# NBMC_SCHEMATIC_with_LBM313.net
KiCad netlist of a schematic drawn in EAGLE
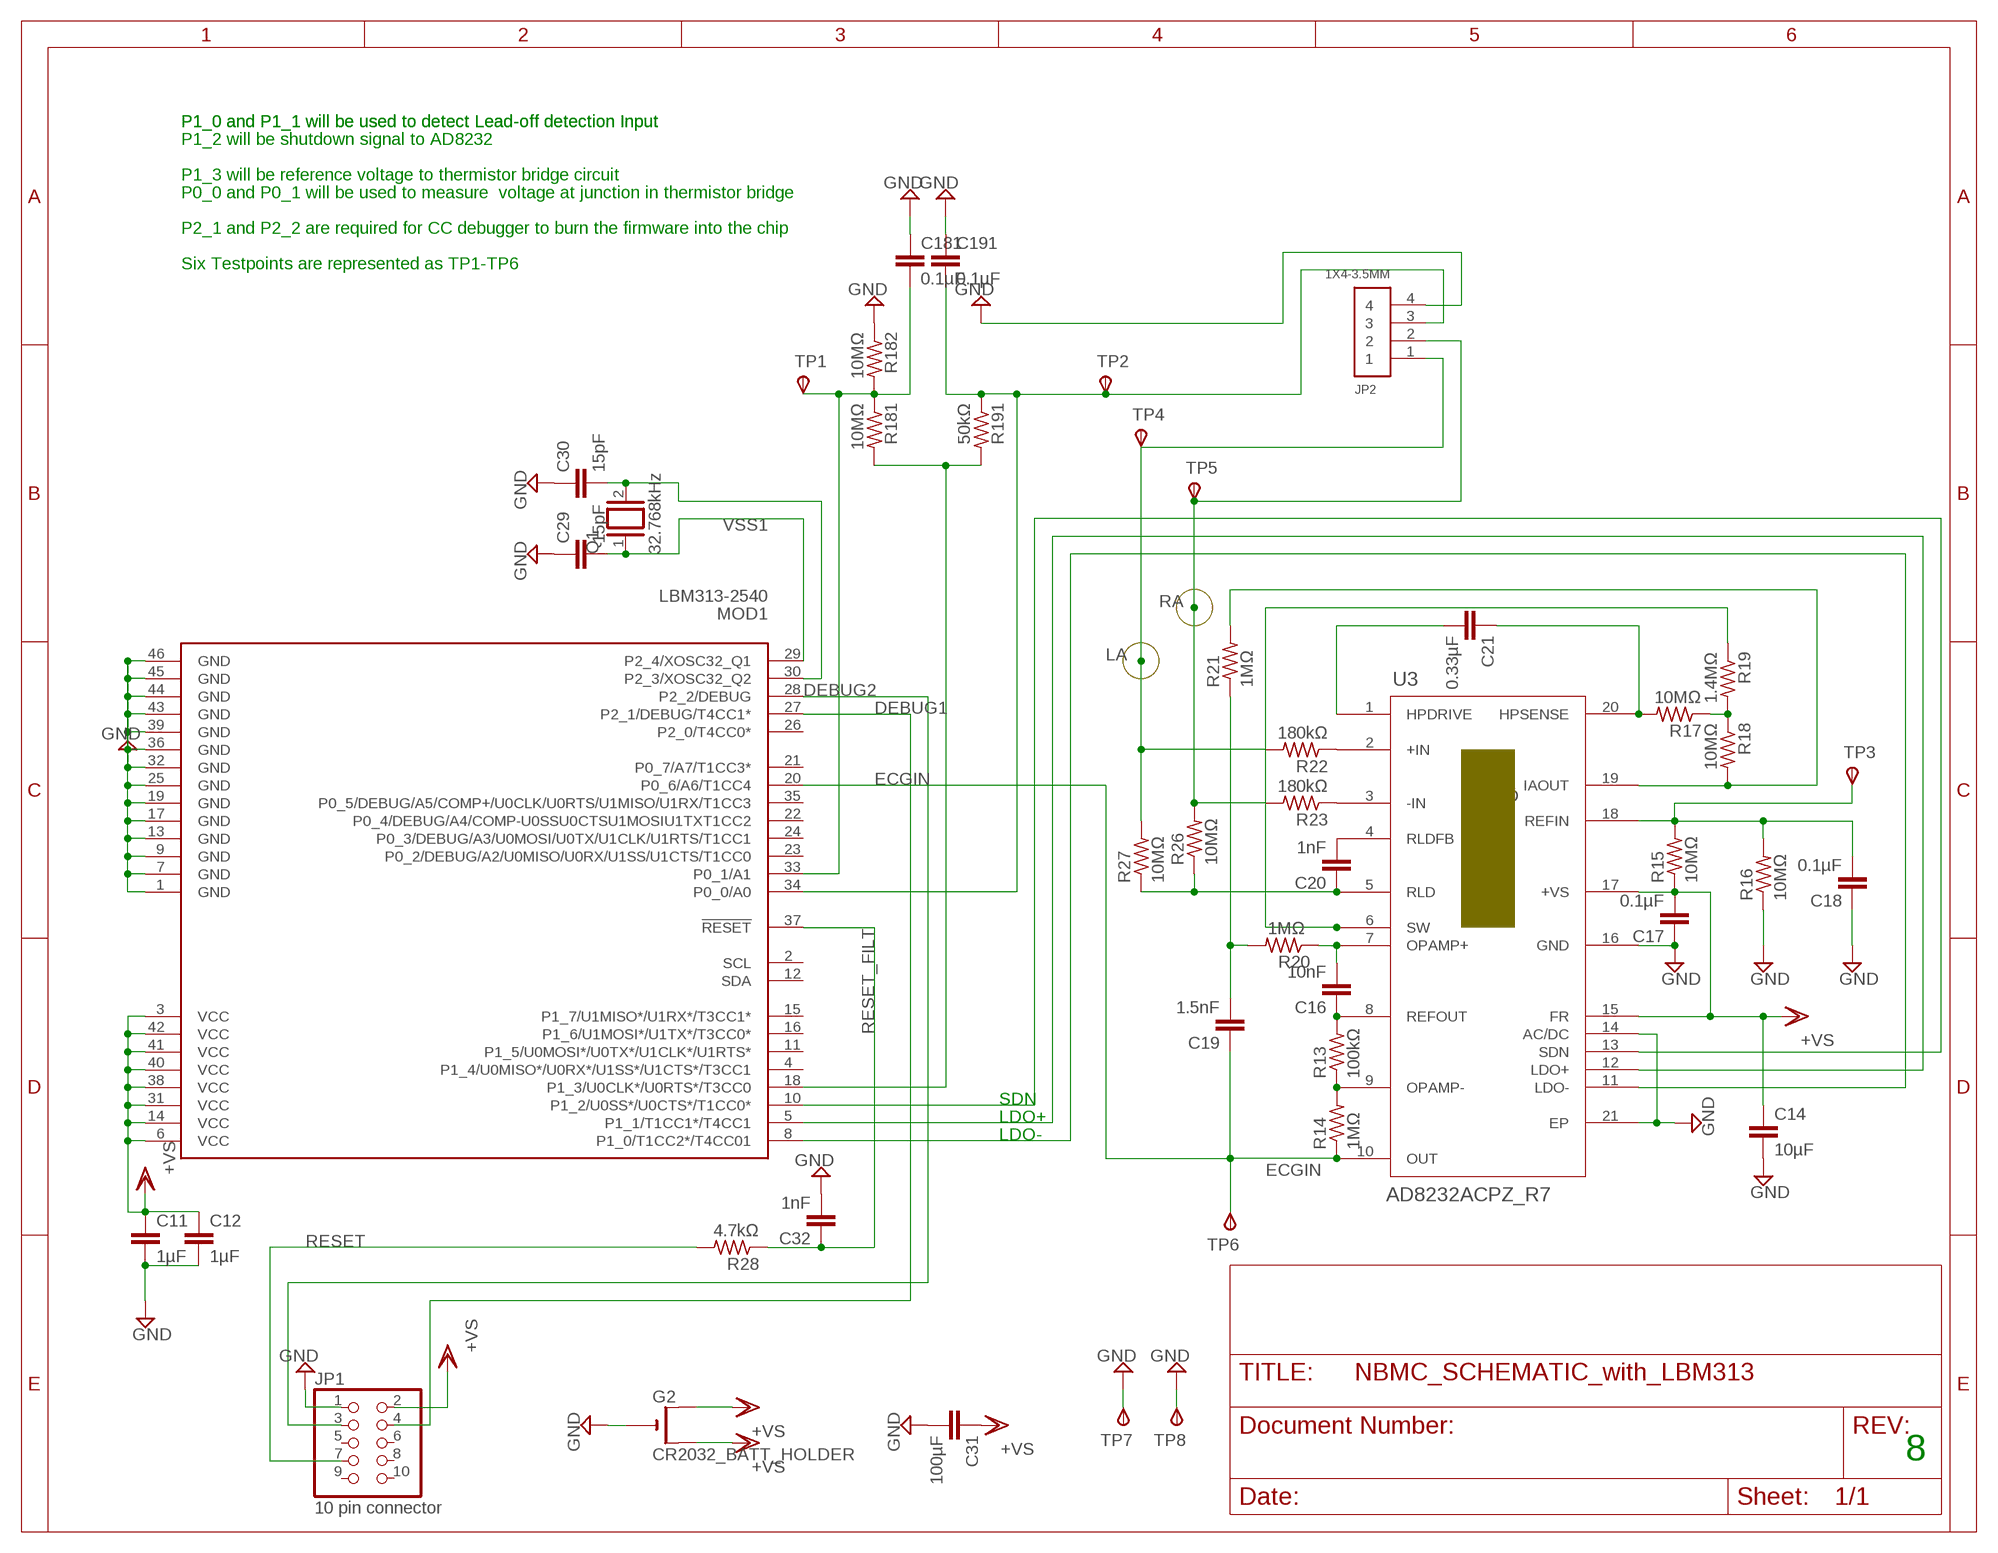
[diagram p0: schematic, sheet 1]

(export (version "E")
  (design (tool "Eeschema 10.0.6"))
  (components
    (comp (ref "C11")
      (value "1µF")
      (footprint "eagle-import:C0402")
      (libsource (lib "eagle-import") (part "C-EUC0402"))
    )
    (comp (ref "C12")
      (value "1µF")
      (footprint "eagle-import:C0402")
      (libsource (lib "eagle-import") (part "C-EUC0402"))
    )
    (comp (ref "C14")
      (value "10µF")
      (footprint "eagle-import:C0402")
      (libsource (lib "eagle-import") (part "C-EUC0402"))
    )
    (comp (ref "C16")
      (value "10nF")
      (footprint "eagle-import:C0402")
      (libsource (lib "eagle-import") (part "C-EUC0402"))
    )
    (comp (ref "C17")
      (value "0.1µF")
      (footprint "eagle-import:C0402")
      (libsource (lib "eagle-import") (part "C-EUC0402"))
    )
    (comp (ref "C18")
      (value "0.1µF")
      (footprint "eagle-import:C0402")
      (libsource (lib "eagle-import") (part "C-EUC0402"))
    )
    (comp (ref "C19")
      (value "1.5nF")
      (footprint "eagle-import:C0402")
      (libsource (lib "eagle-import") (part "C-EUC0402"))
    )
    (comp (ref "C20")
      (value "1nF")
      (footprint "eagle-import:C0402")
      (libsource (lib "eagle-import") (part "C-EUC0402"))
    )
    (comp (ref "C21")
      (value "0.33µF")
      (footprint "eagle-import:C0402")
      (libsource (lib "eagle-import") (part "C-EUC0402"))
    )
    (comp (ref "C29")
      (value "15pF")
      (footprint "eagle-import:C0402")
      (libsource (lib "eagle-import") (part "C-EUC0402"))
    )
    (comp (ref "C30")
      (value "15pF")
      (footprint "eagle-import:C0402")
      (libsource (lib "eagle-import") (part "C-EUC0402"))
    )
    (comp (ref "C31")
      (value "100µF")
      (footprint "eagle-import:C1210")
      (libsource (lib "eagle-import") (part "resistor_C-EUC1210"))
    )
    (comp (ref "C32")
      (value "1nF")
      (footprint "eagle-import:C0402")
      (libsource (lib "eagle-import") (part "C-EUC0402"))
    )
    (comp (ref "C181")
      (value "0.1µF")
      (footprint "eagle-import:C0402")
      (libsource (lib "eagle-import") (part "C-EUC0402"))
    )
    (comp (ref "C191")
      (value "0.1µF")
      (footprint "eagle-import:C0402")
      (libsource (lib "eagle-import") (part "C-EUC0402"))
    )
    (comp (ref "G2")
      (value "CR2032_BATT_HOLDER")
      (footprint "eagle-import:CR2032-SMD")
      (libsource (lib "eagle-import") (part "CR2032SMT"))
    )
    (comp (ref "JP1")
      (value "10 pin connector")
      (footprint "eagle-import:2X05")
      (libsource (lib "eagle-import") (part "PINHD-2X5"))
    )
    (comp (ref "JP2")
      (value "1X4-3.5MM")
      (footprint "eagle-import:1X04-3.5MM")
      (libsource (lib "eagle-import") (part "1X4-3.5MM"))
    )
    (comp (ref "MOD1")
      (value "LBM313-2540")
      (footprint "eagle-import:LBM313-2540")
      (libsource (lib "eagle-import") (part "LBM313-2540"))
    )
    (comp (ref "Q1")
      (value "32.768kHz")
      (footprint "eagle-import:Q")
      (libsource (lib "eagle-import") (part "XTAL"))
    )
    (comp (ref "R13")
      (value "100kΩ")
      (footprint "eagle-import:R0402")
      (libsource (lib "eagle-import") (part "R-US_R0402"))
    )
    (comp (ref "R14")
      (value "1MΩ")
      (footprint "eagle-import:R0402")
      (libsource (lib "eagle-import") (part "R-US_R0402"))
    )
    (comp (ref "R15")
      (value "10MΩ")
      (footprint "eagle-import:R0402")
      (libsource (lib "eagle-import") (part "R-US_R0402"))
    )
    (comp (ref "R16")
      (value "10MΩ")
      (footprint "eagle-import:R0402")
      (libsource (lib "eagle-import") (part "R-US_R0402"))
    )
    (comp (ref "R17")
      (value "10MΩ")
      (footprint "eagle-import:R0402")
      (libsource (lib "eagle-import") (part "R-US_R0402"))
    )
    (comp (ref "R18")
      (value "10MΩ")
      (footprint "eagle-import:R0402")
      (libsource (lib "eagle-import") (part "R-US_R0402"))
    )
    (comp (ref "R19")
      (value "1.4MΩ")
      (footprint "eagle-import:R0402")
      (libsource (lib "eagle-import") (part "R-US_R0402"))
    )
    (comp (ref "R20")
      (value "1MΩ")
      (footprint "eagle-import:R0402")
      (libsource (lib "eagle-import") (part "R-US_R0402"))
    )
    (comp (ref "R21")
      (value "1MΩ")
      (footprint "eagle-import:R0402")
      (libsource (lib "eagle-import") (part "R-US_R0402"))
    )
    (comp (ref "R22")
      (value "180kΩ")
      (footprint "eagle-import:R0402")
      (libsource (lib "eagle-import") (part "R-US_R0402"))
    )
    (comp (ref "R23")
      (value "180kΩ")
      (footprint "eagle-import:R0402")
      (libsource (lib "eagle-import") (part "R-US_R0402"))
    )
    (comp (ref "R26")
      (value "10MΩ")
      (footprint "eagle-import:R0402")
      (libsource (lib "eagle-import") (part "R-US_R0402"))
    )
    (comp (ref "R27")
      (value "10MΩ")
      (footprint "eagle-import:R0402")
      (libsource (lib "eagle-import") (part "R-US_R0402"))
    )
    (comp (ref "R28")
      (value "4.7kΩ")
      (footprint "eagle-import:R0402")
      (libsource (lib "eagle-import") (part "R-US_R0402"))
    )
    (comp (ref "R181")
      (value "10MΩ")
      (footprint "eagle-import:R0402")
      (libsource (lib "eagle-import") (part "R-US_R0402"))
    )
    (comp (ref "R182")
      (value "10MΩ")
      (footprint "eagle-import:R0402")
      (libsource (lib "eagle-import") (part "R-US_R0402"))
    )
    (comp (ref "R191")
      (value "50kΩ")
      (footprint "eagle-import:R0402")
      (libsource (lib "eagle-import") (part "R-US_R0402"))
    )
    (comp (ref "TP1")
      (value "TPSTP09R")
      (footprint "eagle-import:TP09R")
      (libsource (lib "eagle-import") (part "TPSTP09R"))
    )
    (comp (ref "TP2")
      (value "TPSTP09R")
      (footprint "eagle-import:TP09R")
      (libsource (lib "eagle-import") (part "TPSTP09R"))
    )
    (comp (ref "TP3")
      (value "TPSTP09R")
      (footprint "eagle-import:TP09R")
      (libsource (lib "eagle-import") (part "TPSTP09R"))
    )
    (comp (ref "TP4")
      (value "TPSTP09R")
      (footprint "eagle-import:TP09R")
      (libsource (lib "eagle-import") (part "TPSTP09R"))
    )
    (comp (ref "TP5")
      (value "TPSTP09R")
      (footprint "eagle-import:TP09R")
      (libsource (lib "eagle-import") (part "TPSTP09R"))
    )
    (comp (ref "TP6")
      (value "TPSTP09R")
      (footprint "eagle-import:TP09R")
      (libsource (lib "eagle-import") (part "TPSTP09R"))
    )
    (comp (ref "TP7")
      (value "TPSTP09R")
      (footprint "eagle-import:TP09R")
      (libsource (lib "eagle-import") (part "TPSTP09R"))
    )
    (comp (ref "TP8")
      (value "TPSTP09R")
      (footprint "eagle-import:TP09R")
      (libsource (lib "eagle-import") (part "TPSTP09R"))
    )
    (comp (ref "U3")
      (value "AD8232ACPZ_R7")
      (footprint "eagle-import:CP_20_10")
      (libsource (lib "eagle-import") (part "AD8232ACPZ_R7"))
    )
  )
  (nets
    (net (code "1") (name "+VS") (class "Default")
      (node (ref "C11") (pin "1") (pinfunction "1_1") (pintype "passive"))
      (node (ref "C12") (pin "1") (pinfunction "1_1") (pintype "passive"))
      (node (ref "C14") (pin "1") (pinfunction "1_1") (pintype "passive"))
      (node (ref "C17") (pin "2") (pinfunction "2_2") (pintype "passive"))
      (node (ref "C31") (pin "1") (pinfunction "1_1") (pintype "passive"))
      (node (ref "G2") (pin "1") (pinfunction "VS1_1") (pintype "passive"))
      (node (ref "G2") (pin "3") (pinfunction "VS2_3") (pintype "passive"))
      (node (ref "JP1") (pin "2") (pinfunction "2_2") (pintype "passive"))
      (node (ref "MOD1") (pin "14") (pinfunction "VCC_14") (pintype "bidirectional"))
      (node (ref "MOD1") (pin "3") (pinfunction "VCC_3") (pintype "bidirectional"))
      (node (ref "MOD1") (pin "31") (pinfunction "VCC_31") (pintype "bidirectional"))
      (node (ref "MOD1") (pin "38") (pinfunction "VCC_38") (pintype "bidirectional"))
      (node (ref "MOD1") (pin "40") (pinfunction "VCC_40") (pintype "bidirectional"))
      (node (ref "MOD1") (pin "41") (pinfunction "VCC_41") (pintype "bidirectional"))
      (node (ref "MOD1") (pin "42") (pinfunction "VCC_42") (pintype "bidirectional"))
      (node (ref "MOD1") (pin "6") (pinfunction "VCC_6") (pintype "bidirectional"))
      (node (ref "R15") (pin "1") (pinfunction "1_1") (pintype "passive"))
      (node (ref "U3") (pin "15") (pinfunction "FR_15") (pintype "passive"))
      (node (ref "U3") (pin "17") (pinfunction "+VS_17") (pintype "passive"))
    )
    (net (code "2") (name "/DEBUG1") (class "Default")
      (node (ref "JP1") (pin "4") (pinfunction "4_4") (pintype "passive"))
      (node (ref "MOD1") (pin "27") (pinfunction "P2_1/DEBUG/T4CC1*_27") (pintype "bidirectional"))
    )
    (net (code "3") (name "/DEBUG2") (class "Default")
      (node (ref "JP1") (pin "3") (pinfunction "3_3") (pintype "passive"))
      (node (ref "MOD1") (pin "28") (pinfunction "P2_2/DEBUG_28") (pintype "bidirectional"))
    )
    (net (code "4") (name "/ECGIN") (class "Default")
      (node (ref "C19") (pin "1") (pinfunction "1_1") (pintype "passive"))
      (node (ref "MOD1") (pin "20") (pinfunction "P0_6/A6/T1CC4_20") (pintype "bidirectional"))
      (node (ref "R14") (pin "1") (pinfunction "1_1") (pintype "passive"))
      (node (ref "TP6") (pin "TP") (pinfunction "PP_TP") (pintype "input"))
      (node (ref "U3") (pin "10") (pinfunction "OUT_10") (pintype "passive"))
    )
    (net (code "5") (name "/LA") (class "Default")
      (node (ref "JP2") (pin "1") (pinfunction "1_1") (pintype "bidirectional"))
      (node (ref "R22") (pin "2") (pinfunction "2_2") (pintype "passive"))
      (node (ref "R27") (pin "2") (pinfunction "2_2") (pintype "passive"))
      (node (ref "TP4") (pin "TP") (pinfunction "PP_TP") (pintype "input"))
    )
    (net (code "6") (name "/RA") (class "Default")
      (node (ref "JP2") (pin "2") (pinfunction "2_2") (pintype "bidirectional"))
      (node (ref "R23") (pin "2") (pinfunction "2_2") (pintype "passive"))
      (node (ref "R26") (pin "2") (pinfunction "2_2") (pintype "passive"))
      (node (ref "TP5") (pin "TP") (pinfunction "PP_TP") (pintype "input"))
    )
    (net (code "7") (name "/RESET") (class "Default")
      (node (ref "JP1") (pin "7") (pinfunction "7_7") (pintype "passive"))
      (node (ref "R28") (pin "2") (pinfunction "2_2") (pintype "passive"))
    )
    (net (code "8") (name "/RESET_FILT") (class "Default")
      (node (ref "C32") (pin "1") (pinfunction "1_1") (pintype "passive"))
      (node (ref "MOD1") (pin "37") (pinfunction "~{RESET}_37") (pintype "bidirectional"))
      (node (ref "R28") (pin "1") (pinfunction "1_1") (pintype "passive"))
    )
    (net (code "9") (name "/VSS1") (class "Default")
      (node (ref "C29") (pin "2") (pinfunction "2_2") (pintype "passive"))
      (node (ref "MOD1") (pin "29") (pinfunction "P2_4/XOSC32_Q1_29") (pintype "bidirectional"))
      (node (ref "Q1") (pin "1") (pinfunction "1_1") (pintype "passive"))
    )
    (net (code "10") (name "GND") (class "Default")
      (node (ref "C11") (pin "2") (pinfunction "2_2") (pintype "passive"))
      (node (ref "C12") (pin "2") (pinfunction "2_2") (pintype "passive"))
      (node (ref "C14") (pin "2") (pinfunction "2_2") (pintype "passive"))
      (node (ref "C17") (pin "1") (pinfunction "1_1") (pintype "passive"))
      (node (ref "C18") (pin "1") (pinfunction "1_1") (pintype "passive"))
      (node (ref "C181") (pin "1") (pinfunction "1_1") (pintype "passive"))
      (node (ref "C191") (pin "1") (pinfunction "1_1") (pintype "passive"))
      (node (ref "C29") (pin "1") (pinfunction "1_1") (pintype "passive"))
      (node (ref "C30") (pin "1") (pinfunction "1_1") (pintype "passive"))
      (node (ref "C31") (pin "2") (pinfunction "2_2") (pintype "passive"))
      (node (ref "C32") (pin "2") (pinfunction "2_2") (pintype "passive"))
      (node (ref "G2") (pin "2") (pinfunction "GND_2") (pintype "passive"))
      (node (ref "JP1") (pin "1") (pinfunction "1_1") (pintype "passive"))
      (node (ref "JP2") (pin "4") (pinfunction "4_4") (pintype "bidirectional"))
      (node (ref "MOD1") (pin "1") (pinfunction "GND_1") (pintype "bidirectional"))
      (node (ref "MOD1") (pin "13") (pinfunction "GND_13") (pintype "bidirectional"))
      (node (ref "MOD1") (pin "17") (pinfunction "GND_17") (pintype "bidirectional"))
      (node (ref "MOD1") (pin "19") (pinfunction "GND_19") (pintype "bidirectional"))
      (node (ref "MOD1") (pin "25") (pinfunction "GND_25") (pintype "bidirectional"))
      (node (ref "MOD1") (pin "32") (pinfunction "GND_32") (pintype "bidirectional"))
      (node (ref "MOD1") (pin "36") (pinfunction "GND_36") (pintype "bidirectional"))
      (node (ref "MOD1") (pin "39") (pinfunction "GND_39") (pintype "bidirectional"))
      (node (ref "MOD1") (pin "43") (pinfunction "GND_43") (pintype "bidirectional"))
      (node (ref "MOD1") (pin "44") (pinfunction "GND_44") (pintype "bidirectional"))
      (node (ref "MOD1") (pin "45") (pinfunction "GND_45") (pintype "bidirectional"))
      (node (ref "MOD1") (pin "46") (pinfunction "GND_46") (pintype "bidirectional"))
      (node (ref "MOD1") (pin "7") (pinfunction "GND_7") (pintype "bidirectional"))
      (node (ref "MOD1") (pin "9") (pinfunction "GND_9") (pintype "bidirectional"))
      (node (ref "R16") (pin "1") (pinfunction "1_1") (pintype "passive"))
      (node (ref "R182") (pin "1") (pinfunction "1_1") (pintype "passive"))
      (node (ref "TP7") (pin "TP") (pinfunction "PP_TP") (pintype "input"))
      (node (ref "TP8") (pin "TP") (pinfunction "PP_TP") (pintype "input"))
      (node (ref "U3") (pin "14") (pinfunction "AC/DC_14") (pintype "passive"))
      (node (ref "U3") (pin "16") (pinfunction "GND_16") (pintype "passive"))
      (node (ref "U3") (pin "21") (pinfunction "EP_21") (pintype "passive"))
    )
    (net (code "11") (name "Net-(C19-Pad2)") (class "Default")
      (node (ref "C19") (pin "2") (pinfunction "2_2") (pintype "passive"))
      (node (ref "R20") (pin "2") (pinfunction "2_2") (pintype "passive"))
      (node (ref "R21") (pin "1") (pinfunction "1_1") (pintype "passive"))
    )
    (net (code "12") (name "Net-(MOD1-P0_0{slash}A0)") (class "Default")
      (node (ref "C191") (pin "2") (pinfunction "2_2") (pintype "passive"))
      (node (ref "JP2") (pin "3") (pinfunction "3_3") (pintype "bidirectional"))
      (node (ref "MOD1") (pin "34") (pinfunction "P0_0/A0_34") (pintype "bidirectional"))
      (node (ref "R191") (pin "1") (pinfunction "1_1") (pintype "passive"))
      (node (ref "TP2") (pin "TP") (pinfunction "PP_TP") (pintype "input"))
    )
    (net (code "13") (name "Net-(MOD1-P0_1{slash}A1)") (class "Default")
      (node (ref "C181") (pin "2") (pinfunction "2_2") (pintype "passive"))
      (node (ref "MOD1") (pin "33") (pinfunction "P0_1/A1_33") (pintype "bidirectional"))
      (node (ref "R181") (pin "1") (pinfunction "1_1") (pintype "passive"))
      (node (ref "R182") (pin "2") (pinfunction "2_2") (pintype "passive"))
      (node (ref "TP1") (pin "TP") (pinfunction "PP_TP") (pintype "input"))
    )
    (net (code "14") (name "Net-(MOD1-P1_0{slash}T1CC2*{slash}T4CC01)") (class "Default")
      (node (ref "MOD1") (pin "8") (pinfunction "P1_0/T1CC2*/T4CC01_8") (pintype "bidirectional"))
      (node (ref "U3") (pin "11") (pinfunction "LDO-_11") (pintype "passive"))
    )
    (net (code "15") (name "Net-(MOD1-P1_1{slash}T1CC1*{slash}T4CC1)") (class "Default")
      (node (ref "MOD1") (pin "5") (pinfunction "P1_1/T1CC1*/T4CC1_5") (pintype "bidirectional"))
      (node (ref "U3") (pin "12") (pinfunction "LDO+_12") (pintype "passive"))
    )
    (net (code "16") (name "Net-(MOD1-P1_2{slash}U0SS*{slash}U0CTS*{slash}T1CC0*)") (class "Default")
      (node (ref "MOD1") (pin "10") (pinfunction "P1_2/U0SS*/U0CTS*/T1CC0*_10") (pintype "bidirectional"))
      (node (ref "U3") (pin "13") (pinfunction "SDN_13") (pintype "passive"))
    )
    (net (code "17") (name "Net-(MOD1-P1_3{slash}U0CLK*{slash}U0RTS*{slash}T3CC0)") (class "Default")
      (node (ref "MOD1") (pin "18") (pinfunction "P1_3/U0CLK*/U0RTS*/T3CC0_18") (pintype "bidirectional"))
      (node (ref "R181") (pin "2") (pinfunction "2_2") (pintype "passive"))
      (node (ref "R191") (pin "2") (pinfunction "2_2") (pintype "passive"))
    )
    (net (code "18") (name "Net-(MOD1-P2_3{slash}XOSC32_Q2)") (class "Default")
      (node (ref "C30") (pin "2") (pinfunction "2_2") (pintype "passive"))
      (node (ref "MOD1") (pin "30") (pinfunction "P2_3/XOSC32_Q2_30") (pintype "bidirectional"))
      (node (ref "Q1") (pin "2") (pinfunction "2_2") (pintype "passive"))
    )
    (net (code "19") (name "Net-(R17-Pad1)") (class "Default")
      (node (ref "R17") (pin "1") (pinfunction "1_1") (pintype "passive"))
      (node (ref "R18") (pin "1") (pinfunction "1_1") (pintype "passive"))
      (node (ref "R19") (pin "2") (pinfunction "2_2") (pintype "passive"))
    )
    (net (code "20") (name "Net-(TP3-PP)") (class "Default")
      (node (ref "C18") (pin "2") (pinfunction "2_2") (pintype "passive"))
      (node (ref "R15") (pin "2") (pinfunction "2_2") (pintype "passive"))
      (node (ref "R16") (pin "2") (pinfunction "2_2") (pintype "passive"))
      (node (ref "TP3") (pin "TP") (pinfunction "PP_TP") (pintype "input"))
      (node (ref "U3") (pin "18") (pinfunction "REFIN_18") (pintype "passive"))
    )
    (net (code "21") (name "Net-(U3-+IN)") (class "Default")
      (node (ref "R22") (pin "1") (pinfunction "1_1") (pintype "passive"))
      (node (ref "U3") (pin "2") (pinfunction "+IN_2") (pintype "passive"))
    )
    (net (code "22") (name "Net-(U3--IN)") (class "Default")
      (node (ref "R23") (pin "1") (pinfunction "1_1") (pintype "passive"))
      (node (ref "U3") (pin "3") (pinfunction "-IN_3") (pintype "passive"))
    )
    (net (code "23") (name "Net-(U3-HPDRIVE)") (class "Default")
      (node (ref "C21") (pin "2") (pinfunction "2_2") (pintype "passive"))
      (node (ref "U3") (pin "1") (pinfunction "HPDRIVE_1") (pintype "passive"))
    )
    (net (code "24") (name "Net-(U3-HPSENSE)") (class "Default")
      (node (ref "C21") (pin "1") (pinfunction "1_1") (pintype "passive"))
      (node (ref "R17") (pin "2") (pinfunction "2_2") (pintype "passive"))
      (node (ref "U3") (pin "20") (pinfunction "HPSENSE_20") (pintype "passive"))
    )
    (net (code "25") (name "Net-(U3-IAOUT)") (class "Default")
      (node (ref "R18") (pin "2") (pinfunction "2_2") (pintype "passive"))
      (node (ref "R21") (pin "2") (pinfunction "2_2") (pintype "passive"))
      (node (ref "U3") (pin "19") (pinfunction "IAOUT_19") (pintype "passive"))
    )
    (net (code "26") (name "Net-(U3-OPAMP+)") (class "Default")
      (node (ref "C16") (pin "2") (pinfunction "2_2") (pintype "passive"))
      (node (ref "R20") (pin "1") (pinfunction "1_1") (pintype "passive"))
      (node (ref "U3") (pin "7") (pinfunction "OPAMP+_7") (pintype "passive"))
    )
    (net (code "27") (name "Net-(U3-OPAMP-)") (class "Default")
      (node (ref "R13") (pin "1") (pinfunction "1_1") (pintype "passive"))
      (node (ref "R14") (pin "2") (pinfunction "2_2") (pintype "passive"))
      (node (ref "U3") (pin "9") (pinfunction "OPAMP-_9") (pintype "passive"))
    )
    (net (code "28") (name "Net-(U3-REFOUT)") (class "Default")
      (node (ref "C16") (pin "1") (pinfunction "1_1") (pintype "passive"))
      (node (ref "R13") (pin "2") (pinfunction "2_2") (pintype "passive"))
      (node (ref "U3") (pin "8") (pinfunction "REFOUT_8") (pintype "passive"))
    )
    (net (code "29") (name "Net-(U3-RLD)") (class "Default")
      (node (ref "C20") (pin "1") (pinfunction "1_1") (pintype "passive"))
      (node (ref "R26") (pin "1") (pinfunction "1_1") (pintype "passive"))
      (node (ref "R27") (pin "1") (pinfunction "1_1") (pintype "passive"))
      (node (ref "U3") (pin "5") (pinfunction "RLD_5") (pintype "passive"))
    )
    (net (code "30") (name "Net-(U3-RLDFB)") (class "Default")
      (node (ref "C20") (pin "2") (pinfunction "2_2") (pintype "passive"))
      (node (ref "U3") (pin "4") (pinfunction "RLDFB_4") (pintype "passive"))
    )
    (net (code "31") (name "Net-(U3-SW)") (class "Default")
      (node (ref "R19") (pin "1") (pinfunction "1_1") (pintype "passive"))
      (node (ref "U3") (pin "6") (pinfunction "SW_6") (pintype "passive"))
    )
    (net (code "32") (name "unconnected-(JP1-Pad5)") (class "Default")
      (node (ref "JP1") (pin "5") (pinfunction "5_5") (pintype "passive"))
    )
    (net (code "33") (name "unconnected-(JP1-Pad6)") (class "Default")
      (node (ref "JP1") (pin "6") (pinfunction "6_6") (pintype "passive"))
    )
    (net (code "34") (name "unconnected-(JP1-Pad8)") (class "Default")
      (node (ref "JP1") (pin "8") (pinfunction "8_8") (pintype "passive"))
    )
    (net (code "35") (name "unconnected-(JP1-Pad9)") (class "Default")
      (node (ref "JP1") (pin "9") (pinfunction "9_9") (pintype "passive"))
    )
    (net (code "36") (name "unconnected-(JP1-Pad10)") (class "Default")
      (node (ref "JP1") (pin "10") (pinfunction "10_10") (pintype "passive"))
    )
    (net (code "37") (name "unconnected-(MOD1-P0_2{slash}DEBUG{slash}A2{slash}U0MISO{slash}U0RX{slash}U1SS{slash}U1CTS{slash}T1CC0-Pad23)") (class "Default")
      (node (ref "MOD1") (pin "23") (pinfunction "P0_2/DEBUG/A2/U0MISO/U0RX/U1SS/U1CTS/T1CC0_23") (pintype "bidirectional"))
    )
    (net (code "38") (name "unconnected-(MOD1-P0_3{slash}DEBUG{slash}A3{slash}U0MOSI{slash}U0TX{slash}U1CLK{slash}U1RTS{slash}T1CC1-Pad24)") (class "Default")
      (node (ref "MOD1") (pin "24") (pinfunction "P0_3/DEBUG/A3/U0MOSI/U0TX/U1CLK/U1RTS/T1CC1_24") (pintype "bidirectional"))
    )
    (net (code "39") (name "unconnected-(MOD1-P0_4{slash}DEBUG{slash}A4{slash}COMP-U0SSU0CTSU1MOSIU1TXT1CC2-Pad22)") (class "Default")
      (node (ref "MOD1") (pin "22") (pinfunction "P0_4/DEBUG/A4/COMP-U0SSU0CTSU1MOSIU1TXT1CC2_22") (pintype "bidirectional"))
    )
    (net (code "40") (name "unconnected-(MOD1-P0_5{slash}DEBUG{slash}A5{slash}COMP+{slash}U0CLK{slash}U0RTS{slash}U1MISO{slash}U1RX{slash}T1CC3-Pad35)") (class "Default")
      (node (ref "MOD1") (pin "35") (pinfunction "P0_5/DEBUG/A5/COMP+/U0CLK/U0RTS/U1MISO/U1RX/T1CC3_35") (pintype "bidirectional"))
    )
    (net (code "41") (name "unconnected-(MOD1-P0_7{slash}A7{slash}T1CC3*-Pad21)") (class "Default")
      (node (ref "MOD1") (pin "21") (pinfunction "P0_7/A7/T1CC3*_21") (pintype "bidirectional"))
    )
    (net (code "42") (name "unconnected-(MOD1-P1_4{slash}U0MISO*{slash}U0RX*{slash}U1SS*{slash}U1CTS*{slash}T3CC1-Pad4)") (class "Default")
      (node (ref "MOD1") (pin "4") (pinfunction "P1_4/U0MISO*/U0RX*/U1SS*/U1CTS*/T3CC1_4") (pintype "bidirectional"))
    )
    (net (code "43") (name "unconnected-(MOD1-P1_5{slash}U0MOSI*{slash}U0TX*{slash}U1CLK*{slash}U1RTS*-Pad11)") (class "Default")
      (node (ref "MOD1") (pin "11") (pinfunction "P1_5/U0MOSI*/U0TX*/U1CLK*/U1RTS*_11") (pintype "bidirectional"))
    )
    (net (code "44") (name "unconnected-(MOD1-P1_6{slash}U1MOSI*{slash}U1TX*{slash}T3CC0*-Pad16)") (class "Default")
      (node (ref "MOD1") (pin "16") (pinfunction "P1_6/U1MOSI*/U1TX*/T3CC0*_16") (pintype "bidirectional"))
    )
    (net (code "45") (name "unconnected-(MOD1-P1_7{slash}U1MISO*{slash}U1RX*{slash}T3CC1*-Pad15)") (class "Default")
      (node (ref "MOD1") (pin "15") (pinfunction "P1_7/U1MISO*/U1RX*/T3CC1*_15") (pintype "bidirectional"))
    )
    (net (code "46") (name "unconnected-(MOD1-P2_0{slash}T4CC0*-Pad26)") (class "Default")
      (node (ref "MOD1") (pin "26") (pinfunction "P2_0/T4CC0*_26") (pintype "bidirectional"))
    )
    (net (code "47") (name "unconnected-(MOD1-SCL-Pad2)") (class "Default")
      (node (ref "MOD1") (pin "2") (pinfunction "SCL_2") (pintype "bidirectional"))
    )
    (net (code "48") (name "unconnected-(MOD1-SDA-Pad12)") (class "Default")
      (node (ref "MOD1") (pin "12") (pinfunction "SDA_12") (pintype "bidirectional"))
    )
  )
)
